# PCBCONVEYOR.net
KiCad netlist of a schematic drawn in EAGLE
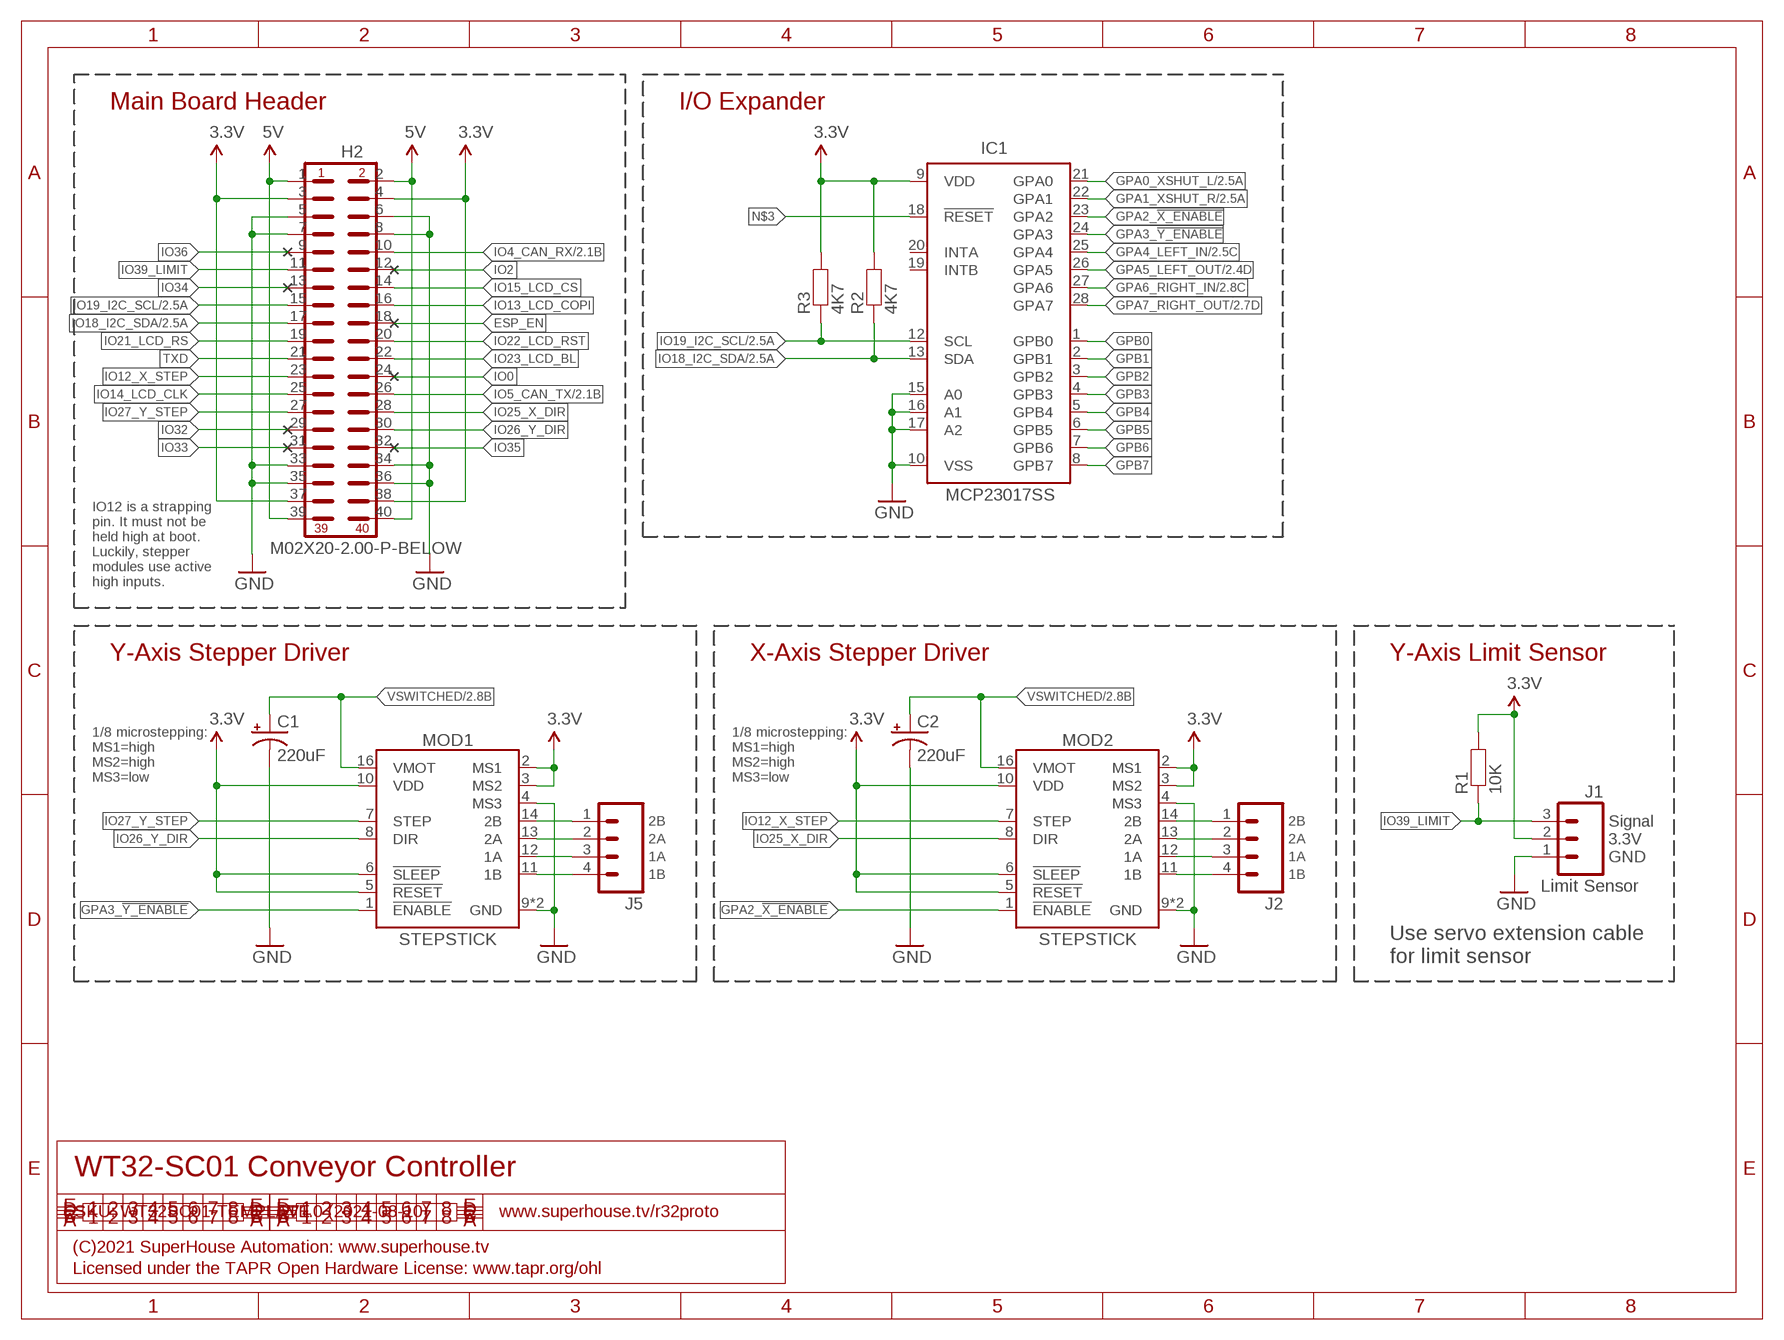
[diagram p0: schematic, sheet 1]
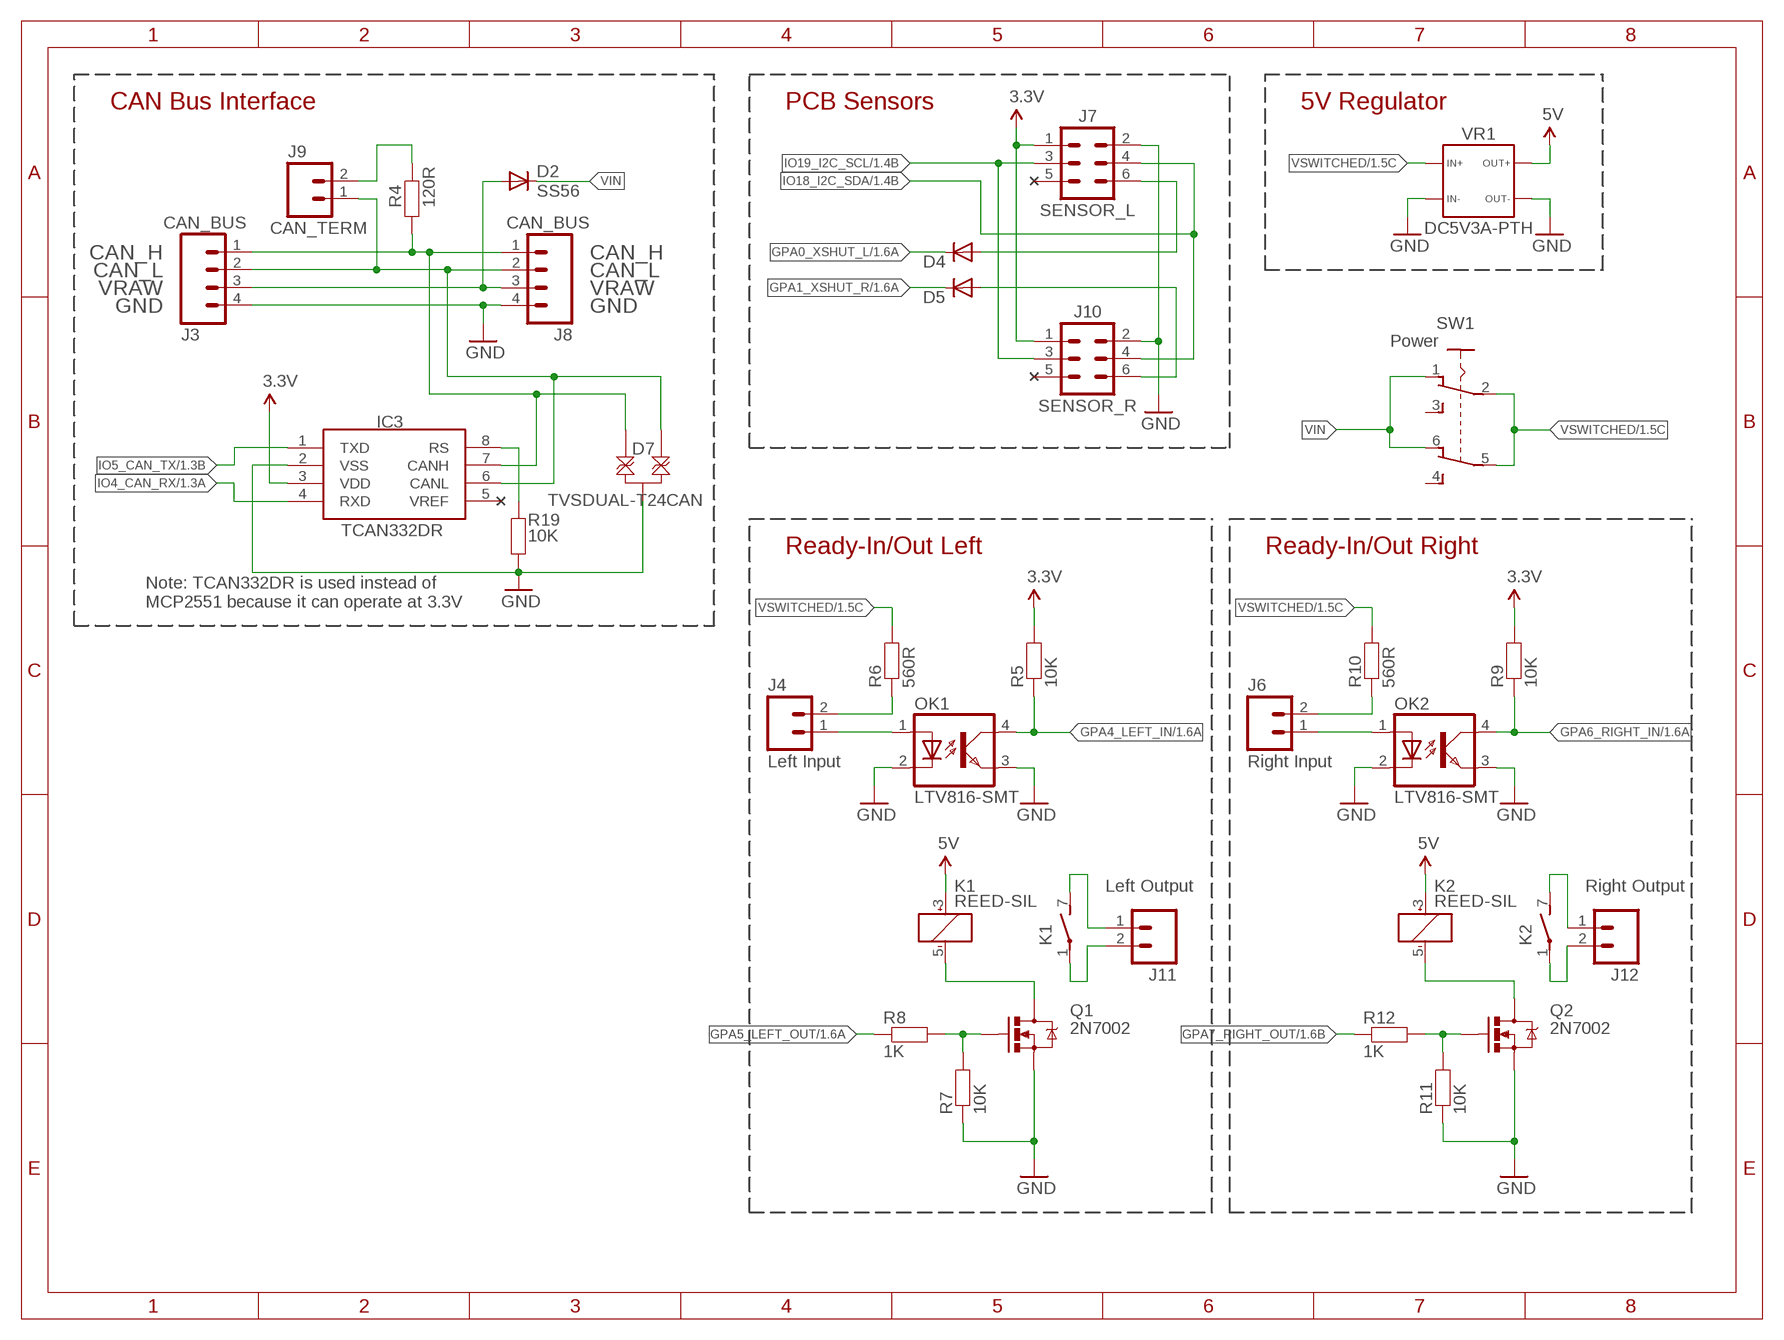
[diagram p1: schematic, sheet 2]

(export (version "E")
  (design (tool "Eeschema 10.0.6"))
  (components
    (comp (ref "D2")
      (value "SS56")
      (footprint "eagle-import:SMA-DIODE")
      (libsource (lib "eagle-import") (part "DIODESMA"))
    )
    (comp (ref "D4")
      (value "DIODESOD")
      (footprint "eagle-import:SOD-323")
      (libsource (lib "eagle-import") (part "DIODESOD"))
    )
    (comp (ref "D5")
      (value "DIODESOD")
      (footprint "eagle-import:SOD-323")
      (libsource (lib "eagle-import") (part "DIODESOD"))
    )
    (comp (ref "D7")
      (value "TVSDUAL-T24CAN")
      (footprint "eagle-import:SOT23-3")
      (libsource (lib "eagle-import") (part "TVSDUAL-T24CAN"))
    )
    (comp (ref "IC3")
      (value "TCAN332DR")
      (footprint "eagle-import:SO08")
      (libsource (lib "eagle-import") (part "MCP2551"))
    )
    (comp (ref "J3")
      (value "CAN_BUS")
      (footprint "eagle-import:SCREWTERMINAL-3.81MM-VERT-4")
      (libsource (lib "eagle-import") (part "M04-SCREW-3.81MM-VERT-PLUG"))
    )
    (comp (ref "J4")
      (value "Left Input")
      (footprint "eagle-import:1X02-KF2510")
      (libsource (lib "eagle-import") (part "M02-KF2510"))
    )
    (comp (ref "J6")
      (value "Right Input")
      (footprint "eagle-import:1X02-KF2510")
      (libsource (lib "eagle-import") (part "M02-KF2510"))
    )
    (comp (ref "J7")
      (value "SENSOR_L")
      (footprint "eagle-import:2X3-2.54-SHROUDED")
      (libsource (lib "eagle-import") (part "M02X3-SHROUDED"))
    )
    (comp (ref "J8")
      (value "CAN_BUS")
      (footprint "eagle-import:SCREWTERMINAL-3.81MM-VERT-4")
      (libsource (lib "eagle-import") (part "M04-SCREW-3.81MM-VERT-PLUG"))
    )
    (comp (ref "J9")
      (value "CAN_TERM")
      (footprint "eagle-import:1X02-P-JUMP-Y")
      (libsource (lib "eagle-import") (part "M02-PIN-JUMP-Y"))
    )
    (comp (ref "J10")
      (value "SENSOR_R")
      (footprint "eagle-import:2X3-2.54-SHROUDED")
      (libsource (lib "eagle-import") (part "M02X3-SHROUDED"))
    )
    (comp (ref "J11")
      (value "Left Output")
      (footprint "eagle-import:1X02-KF2510")
      (libsource (lib "eagle-import") (part "M02-KF2510"))
    )
    (comp (ref "J12")
      (value "Right Output")
      (footprint "eagle-import:1X02-KF2510")
      (libsource (lib "eagle-import") (part "M02-KF2510"))
    )
    (comp (ref "K1")
      (value "REED-SIL")
      (footprint "eagle-import:REED")
      (libsource (lib "eagle-import") (part "REED-SIL"))
    )
    (comp (ref "K2")
      (value "REED-SIL")
      (footprint "eagle-import:REED")
      (libsource (lib "eagle-import") (part "REED-SIL"))
    )
    (comp (ref "OK1")
      (value "LTV816-SMT")
      (footprint "eagle-import:SMD4")
      (libsource (lib "eagle-import") (part "LTV816-SMT"))
    )
    (comp (ref "OK2")
      (value "LTV816-SMT")
      (footprint "eagle-import:SMD4")
      (libsource (lib "eagle-import") (part "LTV816-SMT"))
    )
    (comp (ref "Q1")
      (value "2N7002")
      (footprint "eagle-import:SOT23-3")
      (libsource (lib "eagle-import") (part "MOSFET-NCHANNEL-233"))
    )
    (comp (ref "Q2")
      (value "2N7002")
      (footprint "eagle-import:SOT23-3")
      (libsource (lib "eagle-import") (part "MOSFET-NCHANNEL-233"))
    )
    (comp (ref "R4")
      (value "120R")
      (footprint "eagle-import:R2010")
      (libsource (lib "eagle-import") (part "RESISTOR2010"))
    )
    (comp (ref "R5")
      (value "10K")
      (footprint "eagle-import:R0603")
      (libsource (lib "eagle-import") (part "RESISTOR0603"))
    )
    (comp (ref "R6")
      (value "560R")
      (footprint "eagle-import:R0603")
      (libsource (lib "eagle-import") (part "RESISTOR0603"))
    )
    (comp (ref "R7")
      (value "10K")
      (footprint "eagle-import:R0603")
      (libsource (lib "eagle-import") (part "RESISTOR0603"))
    )
    (comp (ref "R8")
      (value "1K")
      (footprint "eagle-import:R0603")
      (libsource (lib "eagle-import") (part "RESISTOR0603"))
    )
    (comp (ref "R9")
      (value "10K")
      (footprint "eagle-import:R0603")
      (libsource (lib "eagle-import") (part "RESISTOR0603"))
    )
    (comp (ref "R10")
      (value "560R")
      (footprint "eagle-import:R0603")
      (libsource (lib "eagle-import") (part "RESISTOR0603"))
    )
    (comp (ref "R11")
      (value "10K")
      (footprint "eagle-import:R0603")
      (libsource (lib "eagle-import") (part "RESISTOR0603"))
    )
    (comp (ref "R12")
      (value "1K")
      (footprint "eagle-import:R0603")
      (libsource (lib "eagle-import") (part "RESISTOR0603"))
    )
    (comp (ref "R19")
      (value "10K")
      (footprint "eagle-import:R0603")
      (libsource (lib "eagle-import") (part "RESISTOR0603"))
    )
    (comp (ref "SW1")
      (value "Power")
      (footprint "eagle-import:7201SD9AV2BE")
      (libsource (lib "eagle-import") (part "SWITCH-DPDT3"))
    )
    (comp (ref "VR1")
      (value "DC5V3A-PTH")
      (footprint "eagle-import:DC5V3A-PTH")
      (libsource (lib "eagle-import") (part "DC5V3A-PTH"))
    )
    (comp (ref "C1")
      (value "220uF")
      (footprint "eagle-import:CPOL-RADIAL-220UF-50V")
      (libsource (lib "eagle-import") (part "CAP_POLCPOL-RADIAL-220UF-50V"))
    )
    (comp (ref "C2")
      (value "220uF")
      (footprint "eagle-import:CPOL-RADIAL-220UF-50V")
      (libsource (lib "eagle-import") (part "CAP_POLCPOL-RADIAL-220UF-50V"))
    )
    (comp (ref "H2")
      (value "M02X20-2.00-P-BELOW")
      (footprint "eagle-import:2X20-2.00-P-BELOW")
      (libsource (lib "eagle-import") (part "M02X20-2.00-P-BELOW"))
    )
    (comp (ref "IC1")
      (value "MCP23017SS")
      (footprint "eagle-import:SSOP28")
      (libsource (lib "eagle-import") (part "MCP23017SS"))
    )
    (comp (ref "J1")
      (value "Limit Sensor")
      (footprint "eagle-import:1X03-P")
      (libsource (lib "eagle-import") (part "M03-PIN"))
    )
    (comp (ref "J2")
      (value "M04-SCREW-3.81MM-VERT-PLUG")
      (footprint "eagle-import:SCREWTERMINAL-3.81MM-VERT-4")
      (libsource (lib "eagle-import") (part "M04-SCREW-3.81MM-VERT-PLUG"))
    )
    (comp (ref "J5")
      (value "M04-SCREW-3.81MM-VERT-PLUG")
      (footprint "eagle-import:SCREWTERMINAL-3.81MM-VERT-4")
      (libsource (lib "eagle-import") (part "M04-SCREW-3.81MM-VERT-PLUG"))
    )
    (comp (ref "MOD1")
      (value "STEPSTICK")
      (footprint "eagle-import:STEPSTICK")
      (libsource (lib "eagle-import") (part "STEPSTICK"))
    )
    (comp (ref "MOD2")
      (value "STEPSTICK")
      (footprint "eagle-import:STEPSTICK")
      (libsource (lib "eagle-import") (part "STEPSTICK"))
    )
    (comp (ref "R1")
      (value "10K")
      (footprint "eagle-import:R0603")
      (libsource (lib "eagle-import") (part "RESISTOR0603"))
    )
    (comp (ref "R2")
      (value "4K7")
      (footprint "eagle-import:R0603")
      (libsource (lib "eagle-import") (part "RESISTOR0603"))
    )
    (comp (ref "R3")
      (value "4K7")
      (footprint "eagle-import:R0603")
      (libsource (lib "eagle-import") (part "RESISTOR0603"))
    )
  )
  (nets
    (net (code "1") (name "3.3V") (class "Default")
      (node (ref "H2") (pin "3") (pinfunction "3_3") (pintype "passive"))
      (node (ref "H2") (pin "37") (pinfunction "37_37") (pintype "passive"))
      (node (ref "H2") (pin "38") (pinfunction "38_38") (pintype "passive"))
      (node (ref "H2") (pin "4") (pinfunction "4_4") (pintype "passive"))
      (node (ref "IC1") (pin "9") (pinfunction "VDD_9") (pintype "power_in"))
      (node (ref "IC3") (pin "3") (pinfunction "VDD_3") (pintype "bidirectional"))
      (node (ref "J1") (pin "2") (pinfunction "2_2") (pintype "passive"))
      (node (ref "J10") (pin "1") (pinfunction "1_1") (pintype "passive"))
      (node (ref "J7") (pin "1") (pinfunction "1_1") (pintype "passive"))
      (node (ref "MOD1") (pin "10") (pinfunction "VDD_10") (pintype "bidirectional"))
      (node (ref "MOD1") (pin "2") (pinfunction "MS1_2") (pintype "bidirectional"))
      (node (ref "MOD1") (pin "3") (pinfunction "MS2_3") (pintype "bidirectional"))
      (node (ref "MOD1") (pin "5") (pinfunction "~{RESET}_5") (pintype "bidirectional"))
      (node (ref "MOD1") (pin "6") (pinfunction "~{SLEEP}_6") (pintype "bidirectional"))
      (node (ref "MOD2") (pin "10") (pinfunction "VDD_10") (pintype "bidirectional"))
      (node (ref "MOD2") (pin "2") (pinfunction "MS1_2") (pintype "bidirectional"))
      (node (ref "MOD2") (pin "3") (pinfunction "MS2_3") (pintype "bidirectional"))
      (node (ref "MOD2") (pin "5") (pinfunction "~{RESET}_5") (pintype "bidirectional"))
      (node (ref "MOD2") (pin "6") (pinfunction "~{SLEEP}_6") (pintype "bidirectional"))
      (node (ref "R1") (pin "2") (pinfunction "2_2") (pintype "passive"))
      (node (ref "R2") (pin "2") (pinfunction "2_2") (pintype "passive"))
      (node (ref "R3") (pin "2") (pinfunction "2_2") (pintype "passive"))
      (node (ref "R5") (pin "2") (pinfunction "2_2") (pintype "passive"))
      (node (ref "R9") (pin "2") (pinfunction "2_2") (pintype "passive"))
    )
    (net (code "2") (name "5V") (class "Default")
      (node (ref "H2") (pin "1") (pinfunction "1_1") (pintype "passive"))
      (node (ref "H2") (pin "2") (pinfunction "2_2") (pintype "passive"))
      (node (ref "H2") (pin "39") (pinfunction "39_39") (pintype "passive"))
      (node (ref "H2") (pin "40") (pinfunction "40_40") (pintype "passive"))
      (node (ref "K1") (pin "3") (pinfunction "+_3") (pintype "passive"))
      (node (ref "K2") (pin "3") (pinfunction "+_3") (pintype "passive"))
      (node (ref "VR1") (pin "3A") (pinfunction "3_3A") (pintype "bidirectional"))
      (node (ref "VR1") (pin "3B") (pinfunction "3_3B") (pintype "bidirectional"))
    )
    (net (code "3") (name "ESP_EN") (class "Default")
      (node (ref "H2") (pin "18") (pinfunction "18_18") (pintype "passive"))
    )
    (net (code "4") (name "GND") (class "Default")
      (node (ref "C1") (pin "2") (pinfunction "-_2") (pintype "passive"))
      (node (ref "C2") (pin "2") (pinfunction "-_2") (pintype "passive"))
      (node (ref "D7") (pin "3") (pinfunction "3_3") (pintype "passive"))
      (node (ref "H2") (pin "33") (pinfunction "33_33") (pintype "passive"))
      (node (ref "H2") (pin "34") (pinfunction "34_34") (pintype "passive"))
      (node (ref "H2") (pin "35") (pinfunction "35_35") (pintype "passive"))
      (node (ref "H2") (pin "36") (pinfunction "36_36") (pintype "passive"))
      (node (ref "H2") (pin "5") (pinfunction "5_5") (pintype "passive"))
      (node (ref "H2") (pin "6") (pinfunction "6_6") (pintype "passive"))
      (node (ref "H2") (pin "7") (pinfunction "7_7") (pintype "passive"))
      (node (ref "H2") (pin "8") (pinfunction "8_8") (pintype "passive"))
      (node (ref "IC1") (pin "10") (pinfunction "VSS_10") (pintype "power_in"))
      (node (ref "IC1") (pin "15") (pinfunction "A0_15") (pintype "input"))
      (node (ref "IC1") (pin "16") (pinfunction "A1_16") (pintype "input"))
      (node (ref "IC1") (pin "17") (pinfunction "A2_17") (pintype "input"))
      (node (ref "IC3") (pin "2") (pinfunction "VSS_2") (pintype "bidirectional"))
      (node (ref "J1") (pin "1") (pinfunction "1_1") (pintype "passive"))
      (node (ref "J10") (pin "2") (pinfunction "2_2") (pintype "passive"))
      (node (ref "J3") (pin "4") (pinfunction "4_4") (pintype "passive"))
      (node (ref "J7") (pin "2") (pinfunction "2_2") (pintype "passive"))
      (node (ref "J8") (pin "4") (pinfunction "4_4") (pintype "passive"))
      (node (ref "MOD1") (pin "15") (pinfunction "GND_15") (pintype "bidirectional"))
      (node (ref "MOD1") (pin "4") (pinfunction "MS3_4") (pintype "bidirectional"))
      (node (ref "MOD1") (pin "9") (pinfunction "GND_9") (pintype "bidirectional"))
      (node (ref "MOD2") (pin "15") (pinfunction "GND_15") (pintype "bidirectional"))
      (node (ref "MOD2") (pin "4") (pinfunction "MS3_4") (pintype "bidirectional"))
      (node (ref "MOD2") (pin "9") (pinfunction "GND_9") (pintype "bidirectional"))
      (node (ref "OK1") (pin "2") (pinfunction "C_2") (pintype "passive"))
      (node (ref "OK1") (pin "3") (pinfunction "EMIT_3") (pintype "passive"))
      (node (ref "OK2") (pin "2") (pinfunction "C_2") (pintype "passive"))
      (node (ref "OK2") (pin "3") (pinfunction "EMIT_3") (pintype "passive"))
      (node (ref "Q1") (pin "2") (pinfunction "S_2") (pintype "passive"))
      (node (ref "Q2") (pin "2") (pinfunction "S_2") (pintype "passive"))
      (node (ref "R11") (pin "1") (pinfunction "1_1") (pintype "passive"))
      (node (ref "R19") (pin "1") (pinfunction "1_1") (pintype "passive"))
      (node (ref "R7") (pin "1") (pinfunction "1_1") (pintype "passive"))
      (node (ref "VR1") (pin "1A") (pinfunction "1_1A") (pintype "bidirectional"))
      (node (ref "VR1") (pin "1B") (pinfunction "1_1B") (pintype "bidirectional"))
      (node (ref "VR1") (pin "4A") (pinfunction "4_4A") (pintype "bidirectional"))
      (node (ref "VR1") (pin "4B") (pinfunction "4_4B") (pintype "bidirectional"))
    )
    (net (code "5") (name "GPA0_XSHUT_L") (class "Default")
      (node (ref "D4") (pin "1") (pinfunction "C_1") (pintype "passive"))
      (node (ref "IC1") (pin "21") (pinfunction "GPA0_21") (pintype "bidirectional"))
    )
    (net (code "6") (name "GPA1_XSHUT_R") (class "Default")
      (node (ref "D5") (pin "1") (pinfunction "C_1") (pintype "passive"))
      (node (ref "IC1") (pin "22") (pinfunction "GPA1_22") (pintype "bidirectional"))
    )
    (net (code "7") (name "GPA2_~{X_ENABLE}") (class "Default")
      (node (ref "IC1") (pin "23") (pinfunction "GPA2_23") (pintype "bidirectional"))
      (node (ref "MOD2") (pin "1") (pinfunction "~{ENABLE}_1") (pintype "bidirectional"))
    )
    (net (code "8") (name "GPA3_~{Y_ENABLE}") (class "Default")
      (node (ref "IC1") (pin "24") (pinfunction "GPA3_24") (pintype "bidirectional"))
      (node (ref "MOD1") (pin "1") (pinfunction "~{ENABLE}_1") (pintype "bidirectional"))
    )
    (net (code "9") (name "GPA4_LEFT_IN") (class "Default")
      (node (ref "IC1") (pin "25") (pinfunction "GPA4_25") (pintype "bidirectional"))
      (node (ref "OK1") (pin "4") (pinfunction "COL_4") (pintype "passive"))
      (node (ref "R5") (pin "1") (pinfunction "1_1") (pintype "passive"))
    )
    (net (code "10") (name "GPA5_LEFT_OUT") (class "Default")
      (node (ref "IC1") (pin "26") (pinfunction "GPA5_26") (pintype "bidirectional"))
      (node (ref "R8") (pin "1") (pinfunction "1_1") (pintype "passive"))
    )
    (net (code "11") (name "GPA6_RIGHT_IN") (class "Default")
      (node (ref "IC1") (pin "27") (pinfunction "GPA6_27") (pintype "bidirectional"))
      (node (ref "OK2") (pin "4") (pinfunction "COL_4") (pintype "passive"))
      (node (ref "R9") (pin "1") (pinfunction "1_1") (pintype "passive"))
    )
    (net (code "12") (name "GPA7_RIGHT_OUT") (class "Default")
      (node (ref "IC1") (pin "28") (pinfunction "GPA7_28") (pintype "bidirectional"))
      (node (ref "R12") (pin "1") (pinfunction "1_1") (pintype "passive"))
    )
    (net (code "13") (name "GPB0") (class "Default")
      (node (ref "IC1") (pin "1") (pinfunction "GPB0_1") (pintype "bidirectional"))
    )
    (net (code "14") (name "GPB1") (class "Default")
      (node (ref "IC1") (pin "2") (pinfunction "GPB1_2") (pintype "bidirectional"))
    )
    (net (code "15") (name "GPB2") (class "Default")
      (node (ref "IC1") (pin "3") (pinfunction "GPB2_3") (pintype "bidirectional"))
    )
    (net (code "16") (name "GPB3") (class "Default")
      (node (ref "IC1") (pin "4") (pinfunction "GPB3_4") (pintype "bidirectional"))
    )
    (net (code "17") (name "GPB4") (class "Default")
      (node (ref "IC1") (pin "5") (pinfunction "GPB4_5") (pintype "bidirectional"))
    )
    (net (code "18") (name "GPB5") (class "Default")
      (node (ref "IC1") (pin "6") (pinfunction "GPB5_6") (pintype "bidirectional"))
    )
    (net (code "19") (name "GPB6") (class "Default")
      (node (ref "IC1") (pin "7") (pinfunction "GPB6_7") (pintype "bidirectional"))
    )
    (net (code "20") (name "GPB7") (class "Default")
      (node (ref "IC1") (pin "8") (pinfunction "GPB7_8") (pintype "bidirectional"))
    )
    (net (code "21") (name "IO0") (class "Default")
      (node (ref "H2") (pin "24") (pinfunction "24_24") (pintype "passive"))
    )
    (net (code "22") (name "IO2") (class "Default")
      (node (ref "H2") (pin "12") (pinfunction "12_12") (pintype "passive"))
    )
    (net (code "23") (name "IO4_CAN_RX") (class "Default")
      (node (ref "H2") (pin "10") (pinfunction "10_10") (pintype "passive"))
      (node (ref "IC3") (pin "4") (pinfunction "RXD_4") (pintype "bidirectional"))
    )
    (net (code "24") (name "IO5_CAN_TX") (class "Default")
      (node (ref "H2") (pin "26") (pinfunction "26_26") (pintype "passive"))
      (node (ref "IC3") (pin "1") (pinfunction "TXD_1") (pintype "bidirectional"))
    )
    (net (code "25") (name "IO12_X_STEP") (class "Default")
      (node (ref "H2") (pin "23") (pinfunction "23_23") (pintype "passive"))
      (node (ref "MOD2") (pin "7") (pinfunction "STEP_7") (pintype "bidirectional"))
    )
    (net (code "26") (name "IO13_LCD_COPI") (class "Default")
      (node (ref "H2") (pin "16") (pinfunction "16_16") (pintype "passive"))
    )
    (net (code "27") (name "IO14_LCD_CLK") (class "Default")
      (node (ref "H2") (pin "25") (pinfunction "25_25") (pintype "passive"))
    )
    (net (code "28") (name "IO15_LCD_CS") (class "Default")
      (node (ref "H2") (pin "14") (pinfunction "14_14") (pintype "passive"))
    )
    (net (code "29") (name "IO18_I2C_SDA") (class "Default")
      (node (ref "H2") (pin "17") (pinfunction "17_17") (pintype "passive"))
      (node (ref "IC1") (pin "13") (pinfunction "SDA_13") (pintype "bidirectional"))
      (node (ref "J10") (pin "4") (pinfunction "4_4") (pintype "passive"))
      (node (ref "J7") (pin "4") (pinfunction "4_4") (pintype "passive"))
      (node (ref "R2") (pin "1") (pinfunction "1_1") (pintype "passive"))
    )
    (net (code "30") (name "IO19_I2C_SCL") (class "Default")
      (node (ref "H2") (pin "15") (pinfunction "15_15") (pintype "passive"))
      (node (ref "IC1") (pin "12") (pinfunction "SCL_12") (pintype "input"))
      (node (ref "J10") (pin "3") (pinfunction "3_3") (pintype "passive"))
      (node (ref "J7") (pin "3") (pinfunction "3_3") (pintype "passive"))
      (node (ref "R3") (pin "1") (pinfunction "1_1") (pintype "passive"))
    )
    (net (code "31") (name "IO21_LCD_RS") (class "Default")
      (node (ref "H2") (pin "19") (pinfunction "19_19") (pintype "passive"))
    )
    (net (code "32") (name "IO22_LCD_RST") (class "Default")
      (node (ref "H2") (pin "20") (pinfunction "20_20") (pintype "passive"))
    )
    (net (code "33") (name "IO23_LCD_BL") (class "Default")
      (node (ref "H2") (pin "22") (pinfunction "22_22") (pintype "passive"))
    )
    (net (code "34") (name "IO25_X_DIR") (class "Default")
      (node (ref "H2") (pin "28") (pinfunction "28_28") (pintype "passive"))
      (node (ref "MOD2") (pin "8") (pinfunction "DIR_8") (pintype "bidirectional"))
    )
    (net (code "35") (name "IO26_Y_DIR") (class "Default")
      (node (ref "H2") (pin "30") (pinfunction "30_30") (pintype "passive"))
      (node (ref "MOD1") (pin "8") (pinfunction "DIR_8") (pintype "bidirectional"))
    )
    (net (code "36") (name "IO27_Y_STEP") (class "Default")
      (node (ref "H2") (pin "27") (pinfunction "27_27") (pintype "passive"))
      (node (ref "MOD1") (pin "7") (pinfunction "STEP_7") (pintype "bidirectional"))
    )
    (net (code "37") (name "IO32") (class "Default")
      (node (ref "H2") (pin "29") (pinfunction "29_29") (pintype "passive"))
    )
    (net (code "38") (name "IO33") (class "Default")
      (node (ref "H2") (pin "31") (pinfunction "31_31") (pintype "passive"))
    )
    (net (code "39") (name "IO34") (class "Default")
      (node (ref "H2") (pin "13") (pinfunction "13_13") (pintype "passive"))
    )
    (net (code "40") (name "IO35") (class "Default")
      (node (ref "H2") (pin "32") (pinfunction "32_32") (pintype "passive"))
    )
    (net (code "41") (name "IO36") (class "Default")
      (node (ref "H2") (pin "9") (pinfunction "9_9") (pintype "passive"))
    )
    (net (code "42") (name "IO39_LIMIT") (class "Default")
      (node (ref "H2") (pin "11") (pinfunction "11_11") (pintype "passive"))
      (node (ref "J1") (pin "3") (pinfunction "3_3") (pintype "passive"))
      (node (ref "R1") (pin "1") (pinfunction "1_1") (pintype "passive"))
    )
    (net (code "43") (name "N$3") (class "Default")
      (node (ref "IC1") (pin "18") (pinfunction "~{RESET}_18") (pintype "input"))
    )
    (net (code "44") (name "Net-(D2-PadA)") (class "Default")
      (node (ref "D2") (pin "A") (pinfunction "A_A") (pintype "passive"))
      (node (ref "J3") (pin "3") (pinfunction "3_3") (pintype "passive"))
      (node (ref "J8") (pin "3") (pinfunction "3_3") (pintype "passive"))
    )
    (net (code "45") (name "Net-(D4-A)") (class "Default")
      (node (ref "D4") (pin "2") (pinfunction "A_2") (pintype "passive"))
      (node (ref "J7") (pin "6") (pinfunction "6_6") (pintype "passive"))
    )
    (net (code "46") (name "Net-(D5-A)") (class "Default")
      (node (ref "D5") (pin "2") (pinfunction "A_2") (pintype "passive"))
      (node (ref "J10") (pin "6") (pinfunction "6_6") (pintype "passive"))
    )
    (net (code "47") (name "Net-(IC3-CANH)") (class "Default")
      (node (ref "D7") (pin "2") (pinfunction "2_2") (pintype "passive"))
      (node (ref "IC3") (pin "7") (pinfunction "CANH_7") (pintype "bidirectional"))
      (node (ref "J3") (pin "1") (pinfunction "1_1") (pintype "passive"))
      (node (ref "J8") (pin "1") (pinfunction "1_1") (pintype "passive"))
      (node (ref "R4") (pin "1") (pinfunction "1_1") (pintype "passive"))
    )
    (net (code "48") (name "Net-(IC3-CANL)") (class "Default")
      (node (ref "D7") (pin "1") (pinfunction "1_1") (pintype "passive"))
      (node (ref "IC3") (pin "6") (pinfunction "CANL_6") (pintype "bidirectional"))
      (node (ref "J3") (pin "2") (pinfunction "2_2") (pintype "passive"))
      (node (ref "J8") (pin "2") (pinfunction "2_2") (pintype "passive"))
      (node (ref "J9") (pin "1") (pinfunction "1_1") (pintype "passive"))
    )
    (net (code "49") (name "Net-(IC3-RS)") (class "Default")
      (node (ref "IC3") (pin "8") (pinfunction "RS_8") (pintype "bidirectional"))
      (node (ref "R19") (pin "2") (pinfunction "2_2") (pintype "passive"))
    )
    (net (code "50") (name "Net-(J4-Pad2)") (class "Default")
      (node (ref "J4") (pin "2") (pinfunction "2_2") (pintype "passive"))
      (node (ref "R6") (pin "1") (pinfunction "1_1") (pintype "passive"))
    )
    (net (code "51") (name "Net-(J6-Pad2)") (class "Default")
      (node (ref "J6") (pin "2") (pinfunction "2_2") (pintype "passive"))
      (node (ref "R10") (pin "1") (pinfunction "1_1") (pintype "passive"))
    )
    (net (code "52") (name "Net-(J9-Pad2)") (class "Default")
      (node (ref "J9") (pin "2") (pinfunction "2_2") (pintype "passive"))
      (node (ref "R4") (pin "2") (pinfunction "2_2") (pintype "passive"))
    )
    (net (code "53") (name "Net-(K1A--)") (class "Default")
      (node (ref "K1") (pin "5") (pinfunction "-_5") (pintype "passive"))
      (node (ref "Q1") (pin "3") (pinfunction "D_3") (pintype "passive"))
    )
    (net (code "54") (name "Net-(K1B-P)") (class "Default")
      (node (ref "J11") (pin "2") (pinfunction "2_2") (pintype "passive"))
      (node (ref "K1") (pin "1") (pinfunction "P_1") (pintype "passive"))
    )
    (net (code "55") (name "Net-(K1B-S)") (class "Default")
      (node (ref "J11") (pin "1") (pinfunction "1_1") (pintype "passive"))
      (node (ref "K1") (pin "7") (pinfunction "S_7") (pintype "passive"))
    )
    (net (code "56") (name "Net-(K2A--)") (class "Default")
      (node (ref "K2") (pin "5") (pinfunction "-_5") (pintype "passive"))
      (node (ref "Q2") (pin "3") (pinfunction "D_3") (pintype "passive"))
    )
    (net (code "57") (name "Net-(K2B-P)") (class "Default")
      (node (ref "J12") (pin "2") (pinfunction "2_2") (pintype "passive"))
      (node (ref "K2") (pin "1") (pinfunction "P_1") (pintype "passive"))
    )
    (net (code "58") (name "Net-(K2B-S)") (class "Default")
      (node (ref "J12") (pin "1") (pinfunction "1_1") (pintype "passive"))
      (node (ref "K2") (pin "7") (pinfunction "S_7") (pintype "passive"))
    )
    (net (code "59") (name "Net-(MOD1-1A)") (class "Default")
      (node (ref "J5") (pin "3") (pinfunction "3_3") (pintype "passive"))
      (node (ref "MOD1") (pin "12") (pinfunction "1A_12") (pintype "bidirectional"))
    )
    (net (code "60") (name "Net-(MOD1-1B)") (class "Default")
      (node (ref "J5") (pin "4") (pinfunction "4_4") (pintype "passive"))
      (node (ref "MOD1") (pin "11") (pinfunction "1B_11") (pintype "bidirectional"))
    )
    (net (code "61") (name "Net-(MOD1-2A)") (class "Default")
      (node (ref "J5") (pin "2") (pinfunction "2_2") (pintype "passive"))
      (node (ref "MOD1") (pin "13") (pinfunction "2A_13") (pintype "bidirectional"))
    )
    (net (code "62") (name "Net-(MOD1-2B)") (class "Default")
      (node (ref "J5") (pin "1") (pinfunction "1_1") (pintype "passive"))
      (node (ref "MOD1") (pin "14") (pinfunction "2B_14") (pintype "bidirectional"))
    )
    (net (code "63") (name "Net-(MOD2-1A)") (class "Default")
      (node (ref "J2") (pin "3") (pinfunction "3_3") (pintype "passive"))
      (node (ref "MOD2") (pin "12") (pinfunction "1A_12") (pintype "bidirectional"))
    )
    (net (code "64") (name "Net-(MOD2-1B)") (class "Default")
      (node (ref "J2") (pin "4") (pinfunction "4_4") (pintype "passive"))
      (node (ref "MOD2") (pin "11") (pinfunction "1B_11") (pintype "bidirectional"))
    )
    (net (code "65") (name "Net-(MOD2-2A)") (class "Default")
      (node (ref "J2") (pin "2") (pinfunction "2_2") (pintype "passive"))
      (node (ref "MOD2") (pin "13") (pinfunction "2A_13") (pintype "bidirectional"))
    )
    (net (code "66") (name "Net-(MOD2-2B)") (class "Default")
      (node (ref "J2") (pin "1") (pinfunction "1_1") (pintype "passive"))
      (node (ref "MOD2") (pin "14") (pinfunction "2B_14") (pintype "bidirectional"))
    )
    (net (code "67") (name "Net-(OK1-A)") (class "Default")
      (node (ref "J4") (pin "1") (pinfunction "1_1") (pintype "passive"))
      (node (ref "OK1") (pin "1") (pinfunction "A_1") (pintype "passive"))
    )
    (net (code "68") (name "Net-(OK2-A)") (class "Default")
      (node (ref "J6") (pin "1") (pinfunction "1_1") (pintype "passive"))
      (node (ref "OK2") (pin "1") (pinfunction "A_1") (pintype "passive"))
    )
    (net (code "69") (name "Net-(Q1-G)") (class "Default")
      (node (ref "Q1") (pin "1") (pinfunction "G_1") (pintype "passive"))
      (node (ref "R7") (pin "2") (pinfunction "2_2") (pintype "passive"))
      (node (ref "R8") (pin "2") (pinfunction "2_2") (pintype "passive"))
    )
    (net (code "70") (name "Net-(Q2-G)") (class "Default")
      (node (ref "Q2") (pin "1") (pinfunction "G_1") (pintype "passive"))
      (node (ref "R11") (pin "2") (pinfunction "2_2") (pintype "passive"))
      (node (ref "R12") (pin "2") (pinfunction "2_2") (pintype "passive"))
    )
    (net (code "71") (name "TXD") (class "Default")
      (node (ref "H2") (pin "21") (pinfunction "21_21") (pintype "passive"))
    )
    (net (code "72") (name "VIN") (class "Default")
      (node (ref "D2") (pin "C") (pinfunction "C_C") (pintype "passive"))
      (node (ref "SW1") (pin "1") (pinfunction "1_1") (pintype "passive"))
      (node (ref "SW1") (pin "6") (pinfunction "6_6") (pintype "passive"))
    )
    (net (code "73") (name "VSWITCHED") (class "Default")
      (node (ref "C1") (pin "1") (pinfunction "+_1") (pintype "passive"))
      (node (ref "C2") (pin "1") (pinfunction "+_1") (pintype "passive"))
      (node (ref "MOD1") (pin "16") (pinfunction "VMOT_16") (pintype "bidirectional"))
      (node (ref "MOD2") (pin "16") (pinfunction "VMOT_16") (pintype "bidirectional"))
      (node (ref "R10") (pin "2") (pinfunction "2_2") (pintype "passive"))
      (node (ref "R6") (pin "2") (pinfunction "2_2") (pintype "passive"))
      (node (ref "SW1") (pin "2") (pinfunction "2_2") (pintype "passive"))
      (node (ref "SW1") (pin "5") (pinfunction "5_5") (pintype "passive"))
      (node (ref "VR1") (pin "2A") (pinfunction "2_2A") (pintype "bidirectional"))
      (node (ref "VR1") (pin "2B") (pinfunction "2_2B") (pintype "bidirectional"))
    )
    (net (code "74") (name "unconnected-(IC1-INTA-Pad20)") (class "Default")
      (node (ref "IC1") (pin "20") (pinfunction "INTA_20") (pintype "output"))
    )
    (net (code "75") (name "unconnected-(IC1-INTB-Pad19)") (class "Default")
      (node (ref "IC1") (pin "19") (pinfunction "INTB_19") (pintype "output"))
    )
    (net (code "76") (name "unconnected-(IC3-VREF-Pad5)") (class "Default")
      (node (ref "IC3") (pin "5") (pinfunction "VREF_5") (pintype "bidirectional"))
    )
    (net (code "77") (name "unconnected-(J7-Pad5)") (class "Default")
      (node (ref "J7") (pin "5") (pinfunction "5_5") (pintype "passive"))
    )
    (net (code "78") (name "unconnected-(J10-Pad5)") (class "Default")
      (node (ref "J10") (pin "5") (pinfunction "5_5") (pintype "passive"))
    )
    (net (code "79") (name "unconnected-(SW1-Pad3)") (class "Default")
      (node (ref "SW1") (pin "3") (pinfunction "3_3") (pintype "passive"))
    )
    (net (code "80") (name "unconnected-(SW1-Pad4)") (class "Default")
      (node (ref "SW1") (pin "4") (pinfunction "4_4") (pintype "passive"))
    )
  )
)
